# DMUX_JTAG.net
KiCad netlist of a schematic drawn in Altium Designer
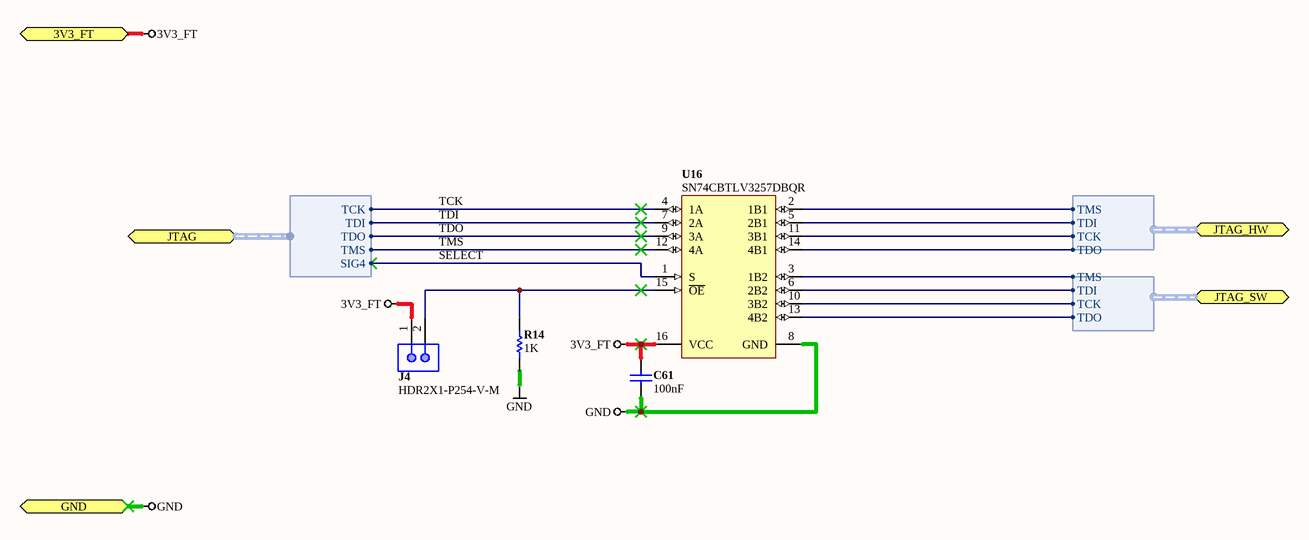
[diagram p0: DMUX_JTAG.SchDoc]

(export (version "E")
  (design (tool "Eeschema 10.0.6"))
  (components
    (comp (ref "C61")
      (value "100nF")
      (footprint "CAPC0402(1005)60_N")
      (description "CAP 100nF 6.3V ?0% 0402 (1005 Metric) Thickness 0.6mm SMD")
      (fields (field (name "TOLERANCE") "?0%") (field (name "Comment") "CAP 100nF 6.3V 0402(1005)"))
      (libsource (lib "Altium Vault") (part "CMP-1034-02062-1"))
    )
    (comp (ref "J4")
      (value "HDR2X1-P254-V-M")
      (footprint "HDR2X1-P254-V-M")
      (description "Male Header IDC, 1 x 2 Pin Vertical 2.54mm Pitch")
      (libsource (lib "Altium Content Vault") (part "CN-1P-M-R2"))
    )
    (comp (ref "R14")
      (value "1K")
      (footprint "RESC0402(1005)_N")
      (description "1K 0.063W 1% 0402 (1005 Metric)  SMD")
      (fields (field (name "TOLERANCE") "1 %") (field (name "POWER") "0.063 W"))
      (libsource (lib "Altium Content Vault") (part "CMP-1011-00510-1"))
    )
    (comp (ref "U16")
      (value "SN74CBTLV3257DBQR")
      (footprint "SSOP-16_N")
      (description "IC QUAD 1:2 FET MUX/DEMUX 16SSOP")
      (libsource (lib "Altium Vault") (part "TI-SN74CBTLV3257_DBQR_16N"))
    )
  )
  (nets
    (net (code "4") (name "/SELECT") (class "Default")
      (node (ref "U16") (pin "1") (pinfunction "S_1") (pintype "input+no_connect"))
    )
    (net (code "5") (name "/TCK") (class "Default")
      (node (ref "U16") (pin "4") (pinfunction "1A_4") (pintype "bidirectional"))
    )
    (net (code "6") (name "/TDI") (class "Default")
      (node (ref "U16") (pin "7") (pinfunction "2A_7") (pintype "bidirectional"))
    )
    (net (code "7") (name "/TDO") (class "Default")
      (node (ref "U16") (pin "9") (pinfunction "3A_9") (pintype "bidirectional"))
    )
    (net (code "8") (name "/TMS") (class "Default")
      (node (ref "U16") (pin "12") (pinfunction "4A_12") (pintype "bidirectional"))
    )
    (net (code "12") (name "3V3_FT") (class "Default")
      (node (ref "C61") (pin "2") (pinfunction "2_2") (pintype "passive"))
      (node (ref "J4") (pin "1") (pinfunction "1_1") (pintype "passive"))
      (node (ref "U16") (pin "16") (pinfunction "VCC_16") (pintype "power_in"))
    )
    (net (code "13") (name "GND") (class "Default")
      (node (ref "C61") (pin "1") (pinfunction "1_1") (pintype "passive"))
      (node (ref "R14") (pin "2") (pinfunction "2_2") (pintype "passive"))
      (node (ref "U16") (pin "8") (pinfunction "GND_8") (pintype "power_in"))
    )
    (net (code "14") (name "Net-(U16-~{OE})") (class "Default")
      (node (ref "J4") (pin "2") (pinfunction "2_2") (pintype "passive"))
      (node (ref "R14") (pin "1") (pinfunction "1_1") (pintype "passive"))
      (node (ref "U16") (pin "15") (pinfunction "~{OE}_15") (pintype "input"))
    )
    (net (code "15") (name "unconnected-(U16-1B1-Pad2)") (class "Default")
      (node (ref "U16") (pin "2") (pinfunction "1B1_2") (pintype "bidirectional"))
    )
    (net (code "16") (name "unconnected-(U16-1B2-Pad3)") (class "Default")
      (node (ref "U16") (pin "3") (pinfunction "1B2_3") (pintype "bidirectional"))
    )
    (net (code "17") (name "unconnected-(U16-2B1-Pad5)") (class "Default")
      (node (ref "U16") (pin "5") (pinfunction "2B1_5") (pintype "bidirectional"))
    )
    (net (code "18") (name "unconnected-(U16-2B2-Pad6)") (class "Default")
      (node (ref "U16") (pin "6") (pinfunction "2B2_6") (pintype "bidirectional"))
    )
    (net (code "19") (name "unconnected-(U16-3B1-Pad11)") (class "Default")
      (node (ref "U16") (pin "11") (pinfunction "3B1_11") (pintype "bidirectional"))
    )
    (net (code "20") (name "unconnected-(U16-3B2-Pad10)") (class "Default")
      (node (ref "U16") (pin "10") (pinfunction "3B2_10") (pintype "bidirectional"))
    )
    (net (code "21") (name "unconnected-(U16-4B1-Pad14)") (class "Default")
      (node (ref "U16") (pin "14") (pinfunction "4B1_14") (pintype "bidirectional"))
    )
    (net (code "22") (name "unconnected-(U16-4B2-Pad13)") (class "Default")
      (node (ref "U16") (pin "13") (pinfunction "4B2_13") (pintype "bidirectional"))
    )
  )
)
